# 03_Ethernet.net
KiCad netlist of a schematic drawn in Altium Designer
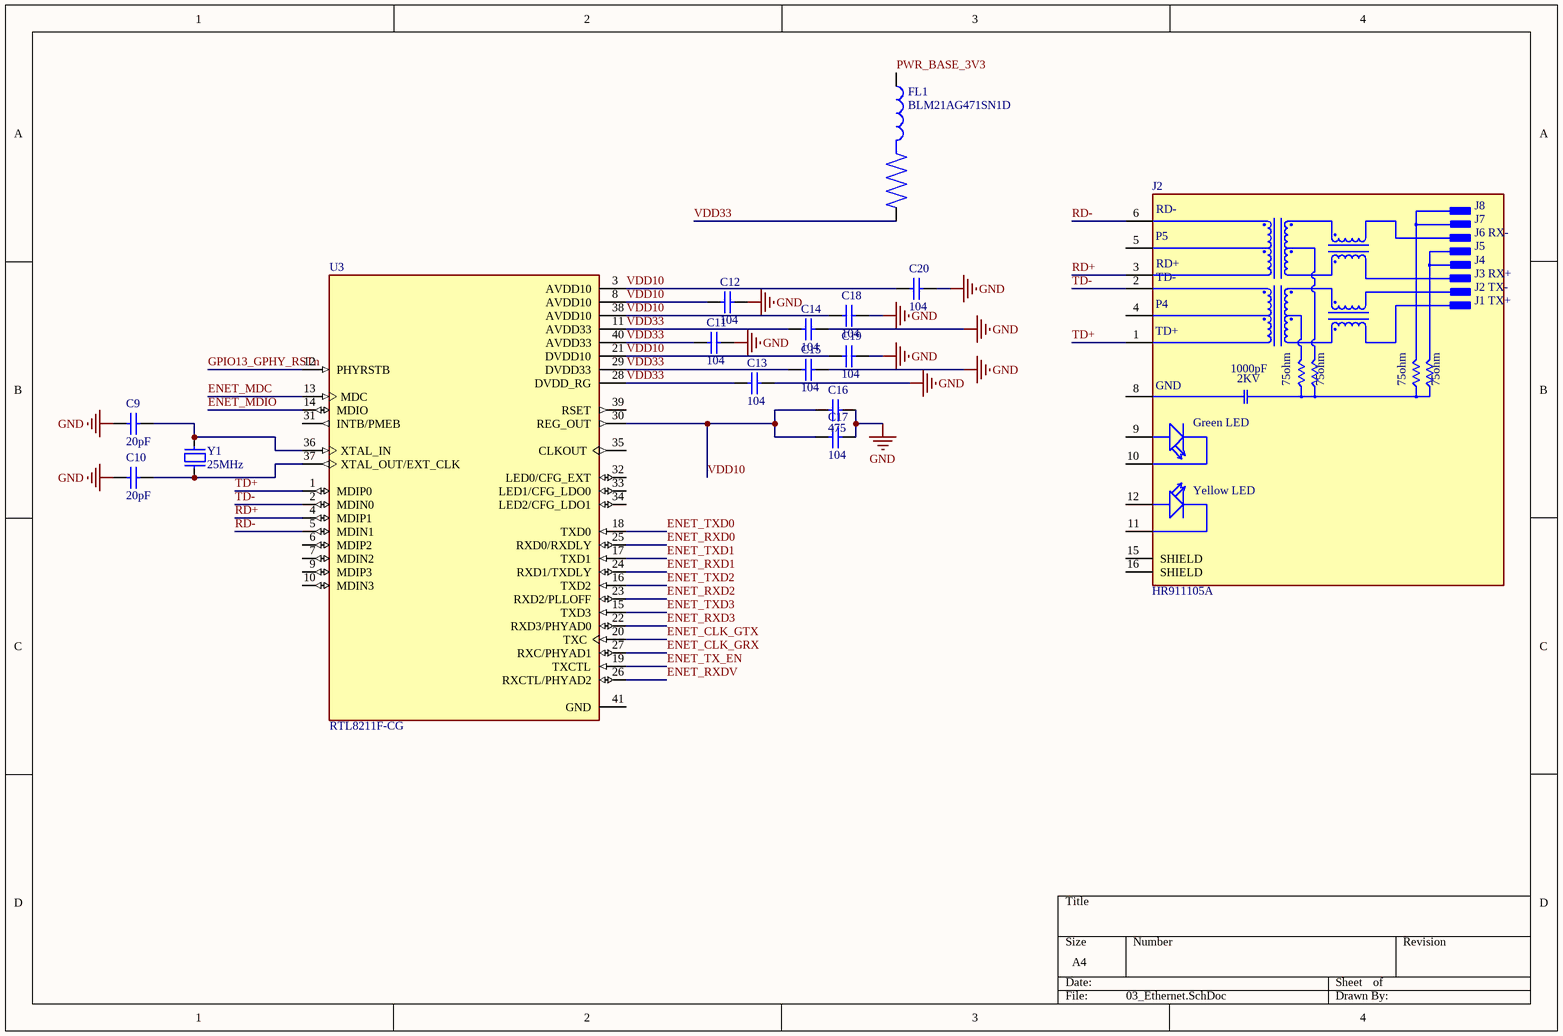
[diagram p0: 03_Ethernet.SchDoc]

(export (version "E")
  (design (tool "Eeschema 10.0.6"))
  (components
    (comp (ref "C9")
      (value "20pF")
      (footprint "tu 0805")
      (description "Dán")
      (libsource (lib "Altium_Lib_by_KhueNguyenCreator") (part "Tu 0805 20pF 50V 10%"))
    )
    (comp (ref "C10")
      (value "20pF")
      (footprint "tu 0805")
      (description "Dán")
      (libsource (lib "Altium_Lib_by_KhueNguyenCreator") (part "Tu 0805 20pF 50V 10%"))
    )
    (comp (ref "C11")
      (value "104")
      (footprint "tu 1206")
      (description "Dán")
      (libsource (lib "Altium_Lib_by_KhueNguyenCreator") (part "Tu 1206 104 50V 20%"))
    )
    (comp (ref "C12")
      (value "104")
      (footprint "tu 1206")
      (description "Dán")
      (libsource (lib "Altium_Lib_by_KhueNguyenCreator") (part "Tu 1206 104 50V 20%"))
    )
    (comp (ref "C13")
      (value "104")
      (footprint "tu 1206")
      (description "Dán")
      (libsource (lib "Altium_Lib_by_KhueNguyenCreator") (part "Tu 1206 104 50V 20%"))
    )
    (comp (ref "C14")
      (value "104")
      (footprint "tu 1206")
      (description "Dán")
      (libsource (lib "Altium_Lib_by_KhueNguyenCreator") (part "Tu 1206 104 50V 20%"))
    )
    (comp (ref "C15")
      (value "104")
      (footprint "tu 1206")
      (description "Dán")
      (libsource (lib "Altium_Lib_by_KhueNguyenCreator") (part "Tu 1206 104 50V 20%"))
    )
    (comp (ref "C16")
      (value "475")
      (footprint "tu 0805")
      (description "Dán")
      (libsource (lib "Altium_Lib_by_KhueNguyenCreator") (part "Tu 0805 475 25V 20%"))
    )
    (comp (ref "C17")
      (value "104")
      (footprint "tu 1206")
      (description "Dán")
      (libsource (lib "Altium_Lib_by_KhueNguyenCreator") (part "Tu 1206 104 50V 20%"))
    )
    (comp (ref "C18")
      (value "104")
      (footprint "tu 1206")
      (description "Dán")
      (libsource (lib "Altium_Lib_by_KhueNguyenCreator") (part "Tu 1206 104 50V 20%"))
    )
    (comp (ref "C19")
      (value "104")
      (footprint "tu 1206")
      (description "Dán")
      (libsource (lib "Altium_Lib_by_KhueNguyenCreator") (part "Tu 1206 104 50V 20%"))
    )
    (comp (ref "C20")
      (value "104")
      (footprint "tu 1206")
      (description "Dán")
      (libsource (lib "Altium_Lib_by_KhueNguyenCreator") (part "Tu 1206 104 50V 20%"))
    )
    (comp (ref "FL1")
      (value "BLM21AG471SN1D")
      (footprint "BEADC2012X105N")
      (description "470 Ohms @ 100MHz 1 Ferrite Bead 0805 _2012 Metric_ 700mA 190mOhm")
      (fields (field (name "MF") "Murata Electronics"))
      (libsource (lib "BLM21AG471SN1D") (part "BLM21AG471SN1D"))
    )
    (comp (ref "J2")
      (value "HR911105A")
      (footprint "HANRUN_HR911105A")
      (description "DIP RJ45 Connector;")
      (fields (field (name "MF") "hanrun"))
      (libsource (lib "HR911105A") (part "HR911105A"))
    )
    (comp (ref "U3")
      (value "RTL8211F-CG")
      (footprint "QFN40P500X500X90-41N")
      (description "GbE PHY with RGMIII interface & EEE feature (Switch Regulator), QFN40")
      (fields (field (name "MF") "Realtek Semiconductor Corp"))
      (libsource (lib "RTL8211F-CG") (part "RTL8211F-CG"))
    )
    (comp (ref "Y1")
      (value "25MHz")
      (footprint "Thach Anh 2 Chan 32,768 KHz")
      (description "Crystal For all Crystal 2pin.")
      (libsource (lib "Altium_Lib_by_KhueNguyenCreator") (part "Thach Anh 2 chan 32,768 Khz"))
    )
  )
  (nets
    (net (code "1") (name "/ENET_CLK_GRX") (class "Default")
      (node (ref "U3") (pin "27") (pinfunction "RXC/PHYAD1_27") (pintype "bidirectional"))
    )
    (net (code "2") (name "/ENET_CLK_GTX") (class "Default")
      (node (ref "U3") (pin "20") (pinfunction "TXC_20") (pintype "input"))
    )
    (net (code "3") (name "/ENET_MDC") (class "Default")
      (node (ref "U3") (pin "13") (pinfunction "MDC_13") (pintype "input"))
    )
    (net (code "4") (name "/ENET_MDIO") (class "Default")
      (node (ref "U3") (pin "14") (pinfunction "MDIO_14") (pintype "bidirectional"))
    )
    (net (code "5") (name "/ENET_RXD0") (class "Default")
      (node (ref "U3") (pin "25") (pinfunction "RXD0/RXDLY_25") (pintype "bidirectional"))
    )
    (net (code "6") (name "/ENET_RXD1") (class "Default")
      (node (ref "U3") (pin "24") (pinfunction "RXD1/TXDLY_24") (pintype "bidirectional"))
    )
    (net (code "7") (name "/ENET_RXD2") (class "Default")
      (node (ref "U3") (pin "23") (pinfunction "RXD2/PLLOFF_23") (pintype "bidirectional"))
    )
    (net (code "8") (name "/ENET_RXD3") (class "Default")
      (node (ref "U3") (pin "22") (pinfunction "RXD3/PHYAD0_22") (pintype "bidirectional"))
    )
    (net (code "9") (name "/ENET_RXDV") (class "Default")
      (node (ref "U3") (pin "26") (pinfunction "RXCTL/PHYAD2_26") (pintype "bidirectional"))
    )
    (net (code "10") (name "/ENET_TXD0") (class "Default")
      (node (ref "U3") (pin "18") (pinfunction "TXD0_18") (pintype "input"))
    )
    (net (code "11") (name "/ENET_TXD1") (class "Default")
      (node (ref "U3") (pin "17") (pinfunction "TXD1_17") (pintype "input"))
    )
    (net (code "12") (name "/ENET_TXD2") (class "Default")
      (node (ref "U3") (pin "16") (pinfunction "TXD2_16") (pintype "input"))
    )
    (net (code "13") (name "/ENET_TXD3") (class "Default")
      (node (ref "U3") (pin "15") (pinfunction "TXD3_15") (pintype "input"))
    )
    (net (code "14") (name "/ENET_TX_EN") (class "Default")
      (node (ref "U3") (pin "19") (pinfunction "TXCTL_19") (pintype "input"))
    )
    (net (code "15") (name "/GPIO13_GPHY_RSTn") (class "Default")
      (node (ref "U3") (pin "12") (pinfunction "PHYRSTB_12") (pintype "input"))
    )
    (net (code "16") (name "/PWR_BASE_3V3") (class "Default")
      (node (ref "FL1") (pin "1") (pinfunction "1_1") (pintype "passive"))
    )
    (net (code "17") (name "/RD+") (class "Default")
      (node (ref "J2") (pin "3") (pinfunction "RD+_3") (pintype "passive"))
      (node (ref "U3") (pin "4") (pinfunction "MDIP1_4") (pintype "bidirectional"))
    )
    (net (code "18") (name "/RD-") (class "Default")
      (node (ref "J2") (pin "6") (pinfunction "RD-_6") (pintype "passive"))
      (node (ref "U3") (pin "5") (pinfunction "MDIN1_5") (pintype "bidirectional"))
    )
    (net (code "19") (name "/TD+") (class "Default")
      (node (ref "J2") (pin "1") (pinfunction "TD+_1") (pintype "passive"))
      (node (ref "U3") (pin "1") (pinfunction "MDIP0_1") (pintype "bidirectional"))
    )
    (net (code "20") (name "/TD-") (class "Default")
      (node (ref "J2") (pin "2") (pinfunction "TD-_2") (pintype "passive"))
      (node (ref "U3") (pin "2") (pinfunction "MDIN0_2") (pintype "bidirectional"))
    )
    (net (code "21") (name "/VDD10") (class "Default")
      (node (ref "C12") (pin "2") (pinfunction "2_2") (pintype "passive"))
      (node (ref "C16") (pin "2") (pinfunction "2_2") (pintype "passive"))
      (node (ref "C17") (pin "2") (pinfunction "2_2") (pintype "passive"))
      (node (ref "C18") (pin "2") (pinfunction "2_2") (pintype "passive"))
      (node (ref "C19") (pin "2") (pinfunction "2_2") (pintype "passive"))
      (node (ref "C20") (pin "2") (pinfunction "2_2") (pintype "passive"))
      (node (ref "U3") (pin "21") (pinfunction "DVDD10_21") (pintype "power_in"))
      (node (ref "U3") (pin "3") (pinfunction "AVDD10_3") (pintype "power_in"))
      (node (ref "U3") (pin "30") (pinfunction "REG_OUT_30") (pintype "output"))
      (node (ref "U3") (pin "38") (pinfunction "AVDD10_38") (pintype "power_in"))
      (node (ref "U3") (pin "8") (pinfunction "AVDD10_8") (pintype "power_in"))
    )
    (net (code "22") (name "/VDD33") (class "Default")
      (node (ref "C11") (pin "2") (pinfunction "2_2") (pintype "passive"))
      (node (ref "C13") (pin "2") (pinfunction "2_2") (pintype "passive"))
      (node (ref "C14") (pin "2") (pinfunction "2_2") (pintype "passive"))
      (node (ref "C15") (pin "2") (pinfunction "2_2") (pintype "passive"))
      (node (ref "FL1") (pin "2") (pinfunction "2_2") (pintype "passive"))
      (node (ref "U3") (pin "11") (pinfunction "AVDD33_11") (pintype "power_in"))
      (node (ref "U3") (pin "28") (pinfunction "DVDD_RG_28") (pintype "power_in"))
      (node (ref "U3") (pin "29") (pinfunction "DVDD33_29") (pintype "power_in"))
      (node (ref "U3") (pin "40") (pinfunction "AVDD33_40") (pintype "power_in"))
    )
    (net (code "23") (name "GND") (class "Default")
      (node (ref "C10") (pin "1") (pinfunction "1_1") (pintype "passive"))
      (node (ref "C11") (pin "1") (pinfunction "1_1") (pintype "passive"))
      (node (ref "C12") (pin "1") (pinfunction "1_1") (pintype "passive"))
      (node (ref "C13") (pin "1") (pinfunction "1_1") (pintype "passive"))
      (node (ref "C14") (pin "1") (pinfunction "1_1") (pintype "passive"))
      (node (ref "C15") (pin "1") (pinfunction "1_1") (pintype "passive"))
      (node (ref "C16") (pin "1") (pinfunction "1_1") (pintype "passive"))
      (node (ref "C17") (pin "1") (pinfunction "1_1") (pintype "passive"))
      (node (ref "C18") (pin "1") (pinfunction "1_1") (pintype "passive"))
      (node (ref "C19") (pin "1") (pinfunction "1_1") (pintype "passive"))
      (node (ref "C20") (pin "1") (pinfunction "1_1") (pintype "passive"))
      (node (ref "C9") (pin "1") (pinfunction "1_1") (pintype "passive"))
    )
    (net (code "24") (name "Net-(U3-XTAL_IN)") (class "Default")
      (node (ref "C9") (pin "2") (pinfunction "2_2") (pintype "passive"))
      (node (ref "U3") (pin "36") (pinfunction "XTAL_IN_36") (pintype "input"))
      (node (ref "Y1") (pin "2") (pinfunction "2_2") (pintype "passive"))
    )
    (net (code "25") (name "Net-(U3-XTAL_OUT{slash}EXT_CLK)") (class "Default")
      (node (ref "C10") (pin "2") (pinfunction "2_2") (pintype "passive"))
      (node (ref "U3") (pin "37") (pinfunction "XTAL_OUT/EXT_CLK_37") (pintype "output"))
      (node (ref "Y1") (pin "1") (pinfunction "1_1") (pintype "passive"))
    )
    (net (code "26") (name "unconnected-(J2-GA-Pad9)") (class "Default")
      (node (ref "J2") (pin "9") (pinfunction "GA_9") (pintype "passive"))
    )
    (net (code "27") (name "unconnected-(J2-GC-Pad10)") (class "Default")
      (node (ref "J2") (pin "10") (pinfunction "GC_10") (pintype "passive"))
    )
    (net (code "28") (name "unconnected-(J2-GND-Pad8)") (class "Default")
      (node (ref "J2") (pin "8") (pinfunction "GND_8") (pintype "power_in"))
    )
    (net (code "29") (name "unconnected-(J2-P4-Pad4)") (class "Default")
      (node (ref "J2") (pin "4") (pinfunction "P4_4") (pintype "passive"))
    )
    (net (code "30") (name "unconnected-(J2-P5-Pad5)") (class "Default")
      (node (ref "J2") (pin "5") (pinfunction "P5_5") (pintype "passive"))
    )
    (net (code "31") (name "unconnected-(J2-SHIELD-Pad15)") (class "Default")
      (node (ref "J2") (pin "15") (pinfunction "SHIELD_15") (pintype "passive"))
    )
    (net (code "32") (name "unconnected-(J2-SHIELD-Pad16)") (class "Default")
      (node (ref "J2") (pin "16") (pinfunction "SHIELD_16") (pintype "passive"))
    )
    (net (code "33") (name "unconnected-(J2-YA-Pad12)") (class "Default")
      (node (ref "J2") (pin "12") (pinfunction "YA_12") (pintype "passive"))
    )
    (net (code "34") (name "unconnected-(J2-YC-Pad11)") (class "Default")
      (node (ref "J2") (pin "11") (pinfunction "YC_11") (pintype "passive"))
    )
    (net (code "35") (name "unconnected-(U3-CLKOUT-Pad35)") (class "Default")
      (node (ref "U3") (pin "35") (pinfunction "CLKOUT_35") (pintype "output"))
    )
    (net (code "36") (name "unconnected-(U3-GND-Pad41)") (class "Default")
      (node (ref "U3") (pin "41") (pinfunction "GND_41") (pintype "power_in"))
    )
    (net (code "37") (name "unconnected-(U3-INTB{slash}PMEB-Pad31)") (class "Default")
      (node (ref "U3") (pin "31") (pinfunction "INTB/PMEB_31") (pintype "output"))
    )
    (net (code "38") (name "unconnected-(U3-LED0{slash}CFG_EXT-Pad32)") (class "Default")
      (node (ref "U3") (pin "32") (pinfunction "LED0/CFG_EXT_32") (pintype "bidirectional"))
    )
    (net (code "39") (name "unconnected-(U3-LED1{slash}CFG_LDO0-Pad33)") (class "Default")
      (node (ref "U3") (pin "33") (pinfunction "LED1/CFG_LDO0_33") (pintype "bidirectional"))
    )
    (net (code "40") (name "unconnected-(U3-LED2{slash}CFG_LDO1-Pad34)") (class "Default")
      (node (ref "U3") (pin "34") (pinfunction "LED2/CFG_LDO1_34") (pintype "bidirectional"))
    )
    (net (code "41") (name "unconnected-(U3-MDIN2-Pad7)") (class "Default")
      (node (ref "U3") (pin "7") (pinfunction "MDIN2_7") (pintype "bidirectional"))
    )
    (net (code "42") (name "unconnected-(U3-MDIN3-Pad10)") (class "Default")
      (node (ref "U3") (pin "10") (pinfunction "MDIN3_10") (pintype "bidirectional"))
    )
    (net (code "43") (name "unconnected-(U3-MDIP2-Pad6)") (class "Default")
      (node (ref "U3") (pin "6") (pinfunction "MDIP2_6") (pintype "bidirectional"))
    )
    (net (code "44") (name "unconnected-(U3-MDIP3-Pad9)") (class "Default")
      (node (ref "U3") (pin "9") (pinfunction "MDIP3_9") (pintype "bidirectional"))
    )
    (net (code "45") (name "unconnected-(U3-RSET-Pad39)") (class "Default")
      (node (ref "U3") (pin "39") (pinfunction "RSET_39") (pintype "output"))
    )
  )
)
